# Adafruit_MAX31856.net
KiCad netlist of a schematic drawn in EAGLE
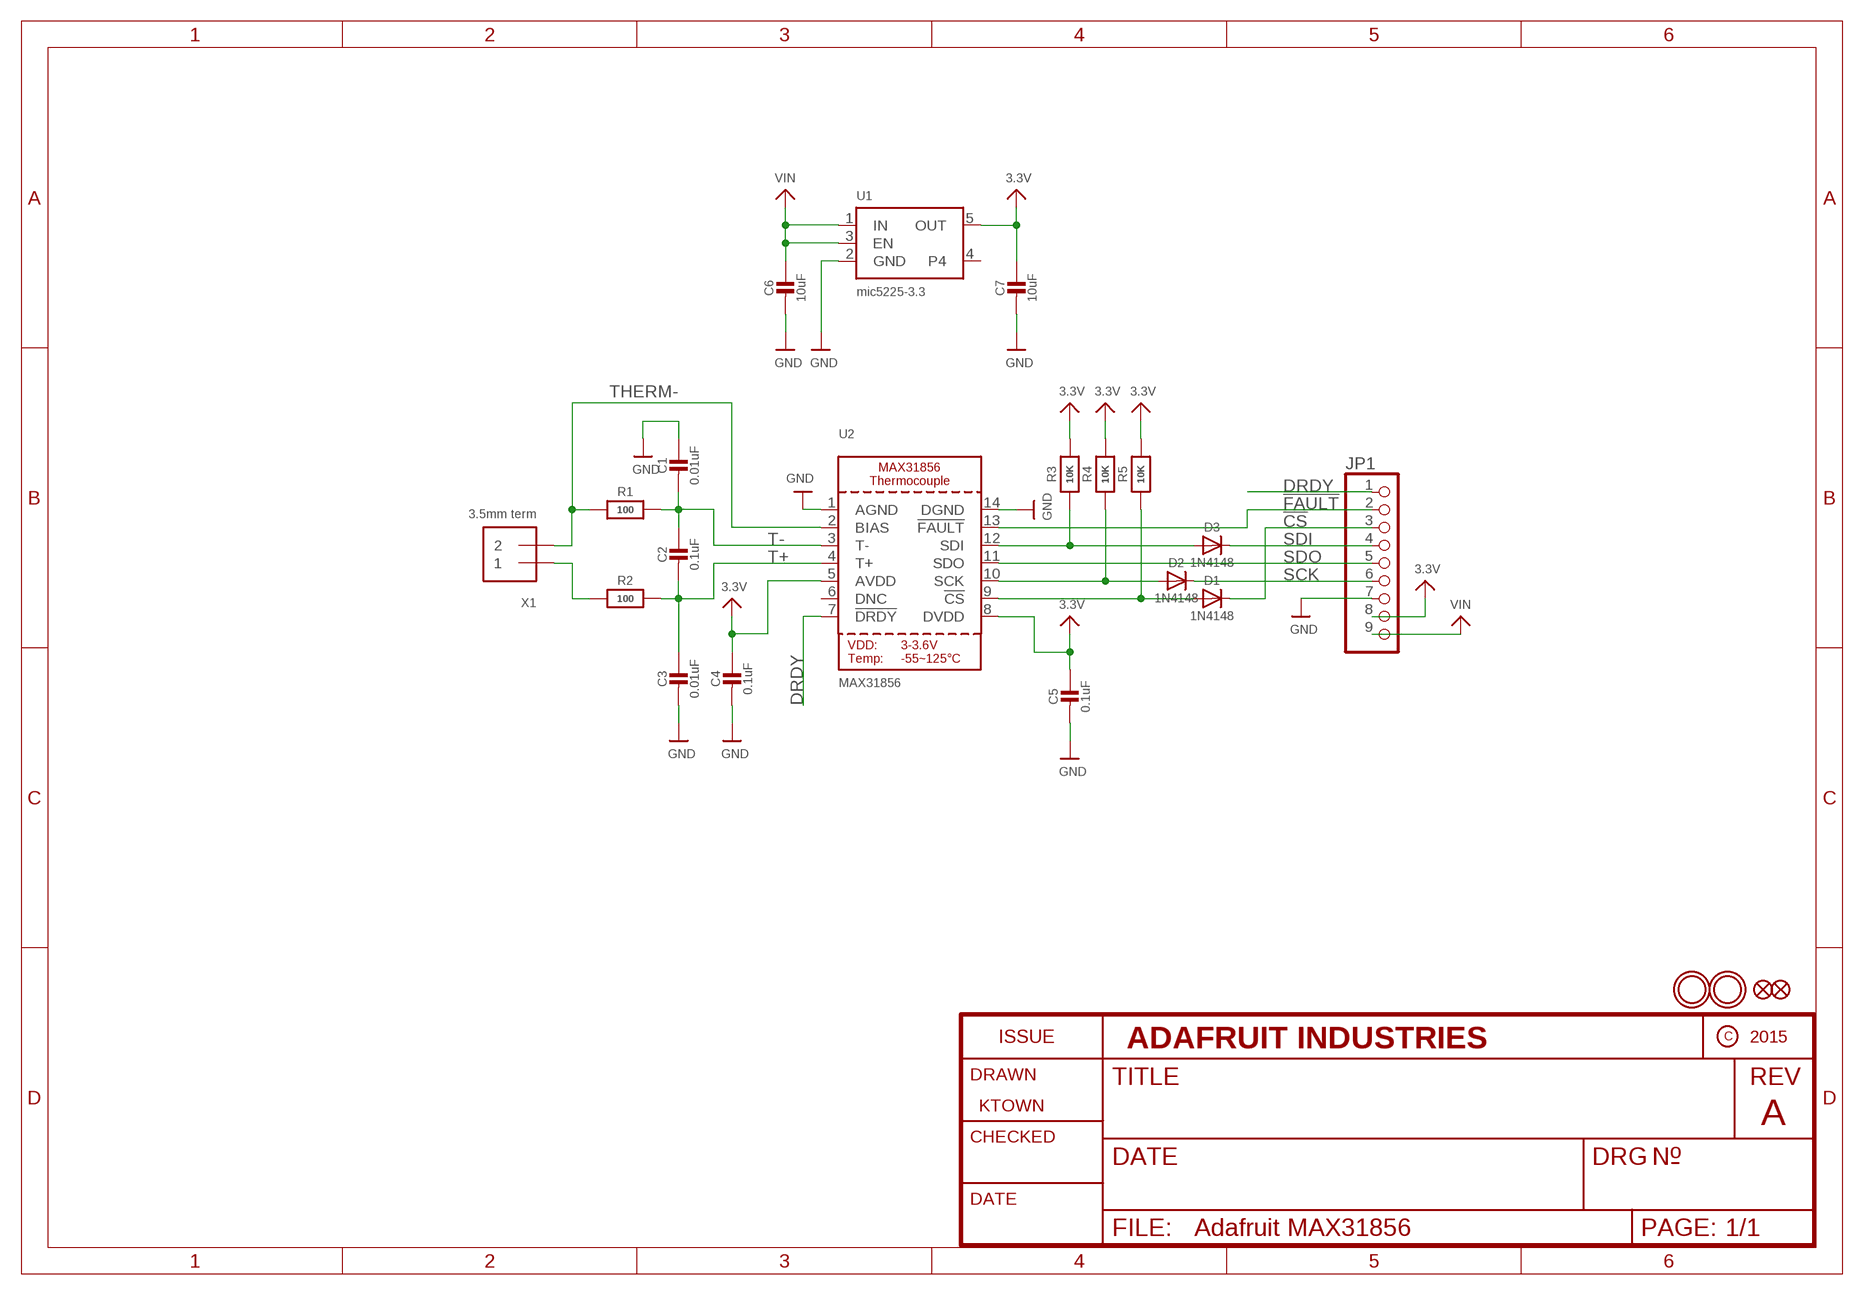
[diagram p0: schematic, sheet 1]

(export (version "E")
  (design (tool "Eeschema 10.0.6"))
  (components
    (comp (ref "C1")
      (value "0.01uF")
      (footprint "eagle-import:0805_10MGAP")
      (libsource (lib "eagle-import") (part "CAP_CERAMIC0805_10MGAP"))
    )
    (comp (ref "C2")
      (value "0.1uF")
      (footprint "eagle-import:0805-NO")
      (libsource (lib "eagle-import") (part "CAP_CERAMIC0805-NOOUTLINE"))
    )
    (comp (ref "C3")
      (value "0.01uF")
      (footprint "eagle-import:0805-NO")
      (libsource (lib "eagle-import") (part "CAP_CERAMIC0805-NOOUTLINE"))
    )
    (comp (ref "C4")
      (value "0.1uF")
      (footprint "eagle-import:0805-NO")
      (libsource (lib "eagle-import") (part "CAP_CERAMIC0805-NOOUTLINE"))
    )
    (comp (ref "C5")
      (value "0.1uF")
      (footprint "eagle-import:0805-NO")
      (libsource (lib "eagle-import") (part "CAP_CERAMIC0805-NOOUTLINE"))
    )
    (comp (ref "C6")
      (value "10uF")
      (footprint "eagle-import:0805-NO")
      (libsource (lib "eagle-import") (part "CAP_CERAMIC0805-NOOUTLINE"))
    )
    (comp (ref "C7")
      (value "10uF")
      (footprint "eagle-import:0805-NO")
      (libsource (lib "eagle-import") (part "CAP_CERAMIC0805-NOOUTLINE"))
    )
    (comp (ref "D1")
      (value "1N4148")
      (footprint "eagle-import:SOD-323")
      (libsource (lib "eagle-import") (part "DIODESOD-323"))
    )
    (comp (ref "D2")
      (value "1N4148")
      (footprint "eagle-import:SOD-323")
      (libsource (lib "eagle-import") (part "DIODESOD-323"))
    )
    (comp (ref "D3")
      (value "1N4148")
      (footprint "eagle-import:SOD-323")
      (libsource (lib "eagle-import") (part "DIODESOD-323"))
    )
    (comp (ref "FID1")
      (value "FIDUCIAL\"\"")
      (footprint "eagle-import:FIDUCIAL_1MM")
      (libsource (lib "eagle-import") (part "FIDUCIAL{dblquote}{dblquote}"))
    )
    (comp (ref "FID2")
      (value "FIDUCIAL\"\"")
      (footprint "eagle-import:FIDUCIAL_1MM")
      (libsource (lib "eagle-import") (part "FIDUCIAL{dblquote}{dblquote}"))
    )
    (comp (ref "JP1")
      (value "HEADER-1X970MIL")
      (footprint "eagle-import:1X09_ROUND_70")
      (libsource (lib "eagle-import") (part "HEADER-1X970MIL"))
    )
    (comp (ref "R1")
      (value "100")
      (footprint "eagle-import:0805-NO")
      (libsource (lib "eagle-import") (part "RESISTOR0805_NOOUTLINE"))
    )
    (comp (ref "R2")
      (value "100")
      (footprint "eagle-import:0805-NO")
      (libsource (lib "eagle-import") (part "RESISTOR0805_NOOUTLINE"))
    )
    (comp (ref "R3")
      (value "10K")
      (footprint "eagle-import:0805-NO")
      (libsource (lib "eagle-import") (part "RESISTOR0805_NOOUTLINE"))
    )
    (comp (ref "R4")
      (value "10K")
      (footprint "eagle-import:0805-NO")
      (libsource (lib "eagle-import") (part "RESISTOR0805_NOOUTLINE"))
    )
    (comp (ref "R5")
      (value "10K")
      (footprint "eagle-import:0805-NO")
      (libsource (lib "eagle-import") (part "RESISTOR0805_NOOUTLINE"))
    )
    (comp (ref "U$13")
      (value "MOUNTINGHOLE2.5")
      (footprint "eagle-import:MOUNTINGHOLE_2.5_PLATED")
      (libsource (lib "eagle-import") (part "MOUNTINGHOLE2.5"))
    )
    (comp (ref "U$14")
      (value "MOUNTINGHOLE2.5")
      (footprint "eagle-import:MOUNTINGHOLE_2.5_PLATED")
      (libsource (lib "eagle-import") (part "MOUNTINGHOLE2.5"))
    )
    (comp (ref "U1")
      (value "mic5225-3.3")
      (footprint "eagle-import:SOT23-5")
      (libsource (lib "eagle-import") (part "VREG_SOT23-5"))
    )
    (comp (ref "U2")
      (value "MAX31856")
      (footprint "eagle-import:TSSOP14")
      (libsource (lib "eagle-import") (part "MAX31856"))
    )
    (comp (ref "X1")
      (value "3.5mm term")
      (footprint "eagle-import:TERMBLOCK_1X2-3.5MM")
      (libsource (lib "eagle-import") (part "TERMBLOCK_1X2"))
    )
  )
  (nets
    (net (code "1") (name "/DRDY") (class "Default")
      (node (ref "JP1") (pin "1") (pinfunction "1_1") (pintype "passive"))
      (node (ref "U2") (pin "7") (pinfunction "~{DRDY}_7") (pintype "output"))
    )
    (net (code "2") (name "/SCK") (class "Default")
      (node (ref "D2") (pin "C") (pinfunction "C_C") (pintype "passive"))
      (node (ref "JP1") (pin "6") (pinfunction "6_6") (pintype "passive"))
    )
    (net (code "3") (name "/SDI") (class "Default")
      (node (ref "D3") (pin "C") (pinfunction "C_C") (pintype "passive"))
      (node (ref "JP1") (pin "4") (pinfunction "4_4") (pintype "passive"))
    )
    (net (code "4") (name "/SDO") (class "Default")
      (node (ref "JP1") (pin "5") (pinfunction "5_5") (pintype "passive"))
      (node (ref "U2") (pin "11") (pinfunction "SDO_11") (pintype "output"))
    )
    (net (code "5") (name "/T+") (class "Default")
      (node (ref "C2") (pin "2") (pinfunction "2_2") (pintype "passive"))
      (node (ref "C3") (pin "1") (pinfunction "1_1") (pintype "passive"))
      (node (ref "R2") (pin "2") (pinfunction "2_2") (pintype "passive"))
      (node (ref "U2") (pin "4") (pinfunction "T+_4") (pintype "input"))
    )
    (net (code "6") (name "/T-") (class "Default")
      (node (ref "C1") (pin "2") (pinfunction "2_2") (pintype "passive"))
      (node (ref "C2") (pin "1") (pinfunction "1_1") (pintype "passive"))
      (node (ref "R1") (pin "2") (pinfunction "2_2") (pintype "passive"))
      (node (ref "U2") (pin "3") (pinfunction "T-_3") (pintype "input"))
    )
    (net (code "7") (name "/THERM-") (class "Default")
      (node (ref "R1") (pin "1") (pinfunction "1_1") (pintype "passive"))
      (node (ref "U2") (pin "2") (pinfunction "BIAS_2") (pintype "power_in"))
      (node (ref "X1") (pin "2") (pinfunction "2_2") (pintype "passive"))
    )
    (net (code "8") (name "/~{CS}") (class "Default")
      (node (ref "D1") (pin "C") (pinfunction "C_C") (pintype "passive"))
      (node (ref "JP1") (pin "3") (pinfunction "3_3") (pintype "passive"))
    )
    (net (code "9") (name "/~{FAULT}") (class "Default")
      (node (ref "JP1") (pin "2") (pinfunction "2_2") (pintype "passive"))
      (node (ref "U2") (pin "13") (pinfunction "~{FAULT}_13") (pintype "output"))
    )
    (net (code "10") (name "3.3V") (class "Default")
      (node (ref "C4") (pin "1") (pinfunction "1_1") (pintype "passive"))
      (node (ref "C5") (pin "1") (pinfunction "1_1") (pintype "passive"))
      (node (ref "C7") (pin "1") (pinfunction "1_1") (pintype "passive"))
      (node (ref "JP1") (pin "8") (pinfunction "8_8") (pintype "passive"))
      (node (ref "R3") (pin "2") (pinfunction "2_2") (pintype "passive"))
      (node (ref "R4") (pin "2") (pinfunction "2_2") (pintype "passive"))
      (node (ref "R5") (pin "2") (pinfunction "2_2") (pintype "passive"))
      (node (ref "U1") (pin "5") (pinfunction "OUT_5") (pintype "power_in"))
      (node (ref "U2") (pin "5") (pinfunction "AVDD_5") (pintype "power_in"))
      (node (ref "U2") (pin "8") (pinfunction "DVDD_8") (pintype "power_in"))
    )
    (net (code "11") (name "GND") (class "Default")
      (node (ref "C1") (pin "1") (pinfunction "1_1") (pintype "passive"))
      (node (ref "C3") (pin "2") (pinfunction "2_2") (pintype "passive"))
      (node (ref "C4") (pin "2") (pinfunction "2_2") (pintype "passive"))
      (node (ref "C5") (pin "2") (pinfunction "2_2") (pintype "passive"))
      (node (ref "C6") (pin "2") (pinfunction "2_2") (pintype "passive"))
      (node (ref "C7") (pin "2") (pinfunction "2_2") (pintype "passive"))
      (node (ref "JP1") (pin "7") (pinfunction "7_7") (pintype "passive"))
      (node (ref "U1") (pin "2") (pinfunction "GND_2") (pintype "power_in"))
      (node (ref "U2") (pin "1") (pinfunction "AGND_1") (pintype "power_in"))
      (node (ref "U2") (pin "14") (pinfunction "DGND_14") (pintype "power_in"))
    )
    (net (code "12") (name "Net-(R2-Pad1)") (class "Default")
      (node (ref "R2") (pin "1") (pinfunction "1_1") (pintype "passive"))
      (node (ref "X1") (pin "1") (pinfunction "1_1") (pintype "passive"))
    )
    (net (code "13") (name "Net-(U2-SCK)") (class "Default")
      (node (ref "D2") (pin "A") (pinfunction "A_A") (pintype "passive"))
      (node (ref "R4") (pin "1") (pinfunction "1_1") (pintype "passive"))
      (node (ref "U2") (pin "10") (pinfunction "SCK_10") (pintype "input"))
    )
    (net (code "14") (name "Net-(U2-SDI)") (class "Default")
      (node (ref "D3") (pin "A") (pinfunction "A_A") (pintype "passive"))
      (node (ref "R3") (pin "1") (pinfunction "1_1") (pintype "passive"))
      (node (ref "U2") (pin "12") (pinfunction "SDI_12") (pintype "input"))
    )
    (net (code "15") (name "Net-(U2-~{CS})") (class "Default")
      (node (ref "D1") (pin "A") (pinfunction "A_A") (pintype "passive"))
      (node (ref "R5") (pin "1") (pinfunction "1_1") (pintype "passive"))
      (node (ref "U2") (pin "9") (pinfunction "~{CS}_9") (pintype "input"))
    )
    (net (code "16") (name "VIN") (class "Default")
      (node (ref "C6") (pin "1") (pinfunction "1_1") (pintype "passive"))
      (node (ref "JP1") (pin "9") (pinfunction "9_9") (pintype "passive"))
      (node (ref "U1") (pin "1") (pinfunction "IN_1") (pintype "power_in"))
      (node (ref "U1") (pin "3") (pinfunction "EN_3") (pintype "input"))
    )
    (net (code "17") (name "unconnected-(U1-P4-Pad4)") (class "Default")
      (node (ref "U1") (pin "4") (pinfunction "P4_4") (pintype "bidirectional"))
    )
    (net (code "18") (name "unconnected-(U2-DNC-Pad6)") (class "Default")
      (node (ref "U2") (pin "6") (pinfunction "DNC_6") (pintype "no_connect"))
    )
  )
)
